# T5400_Barometer_Breakout-v01.net
KiCad netlist of a schematic drawn in EAGLE
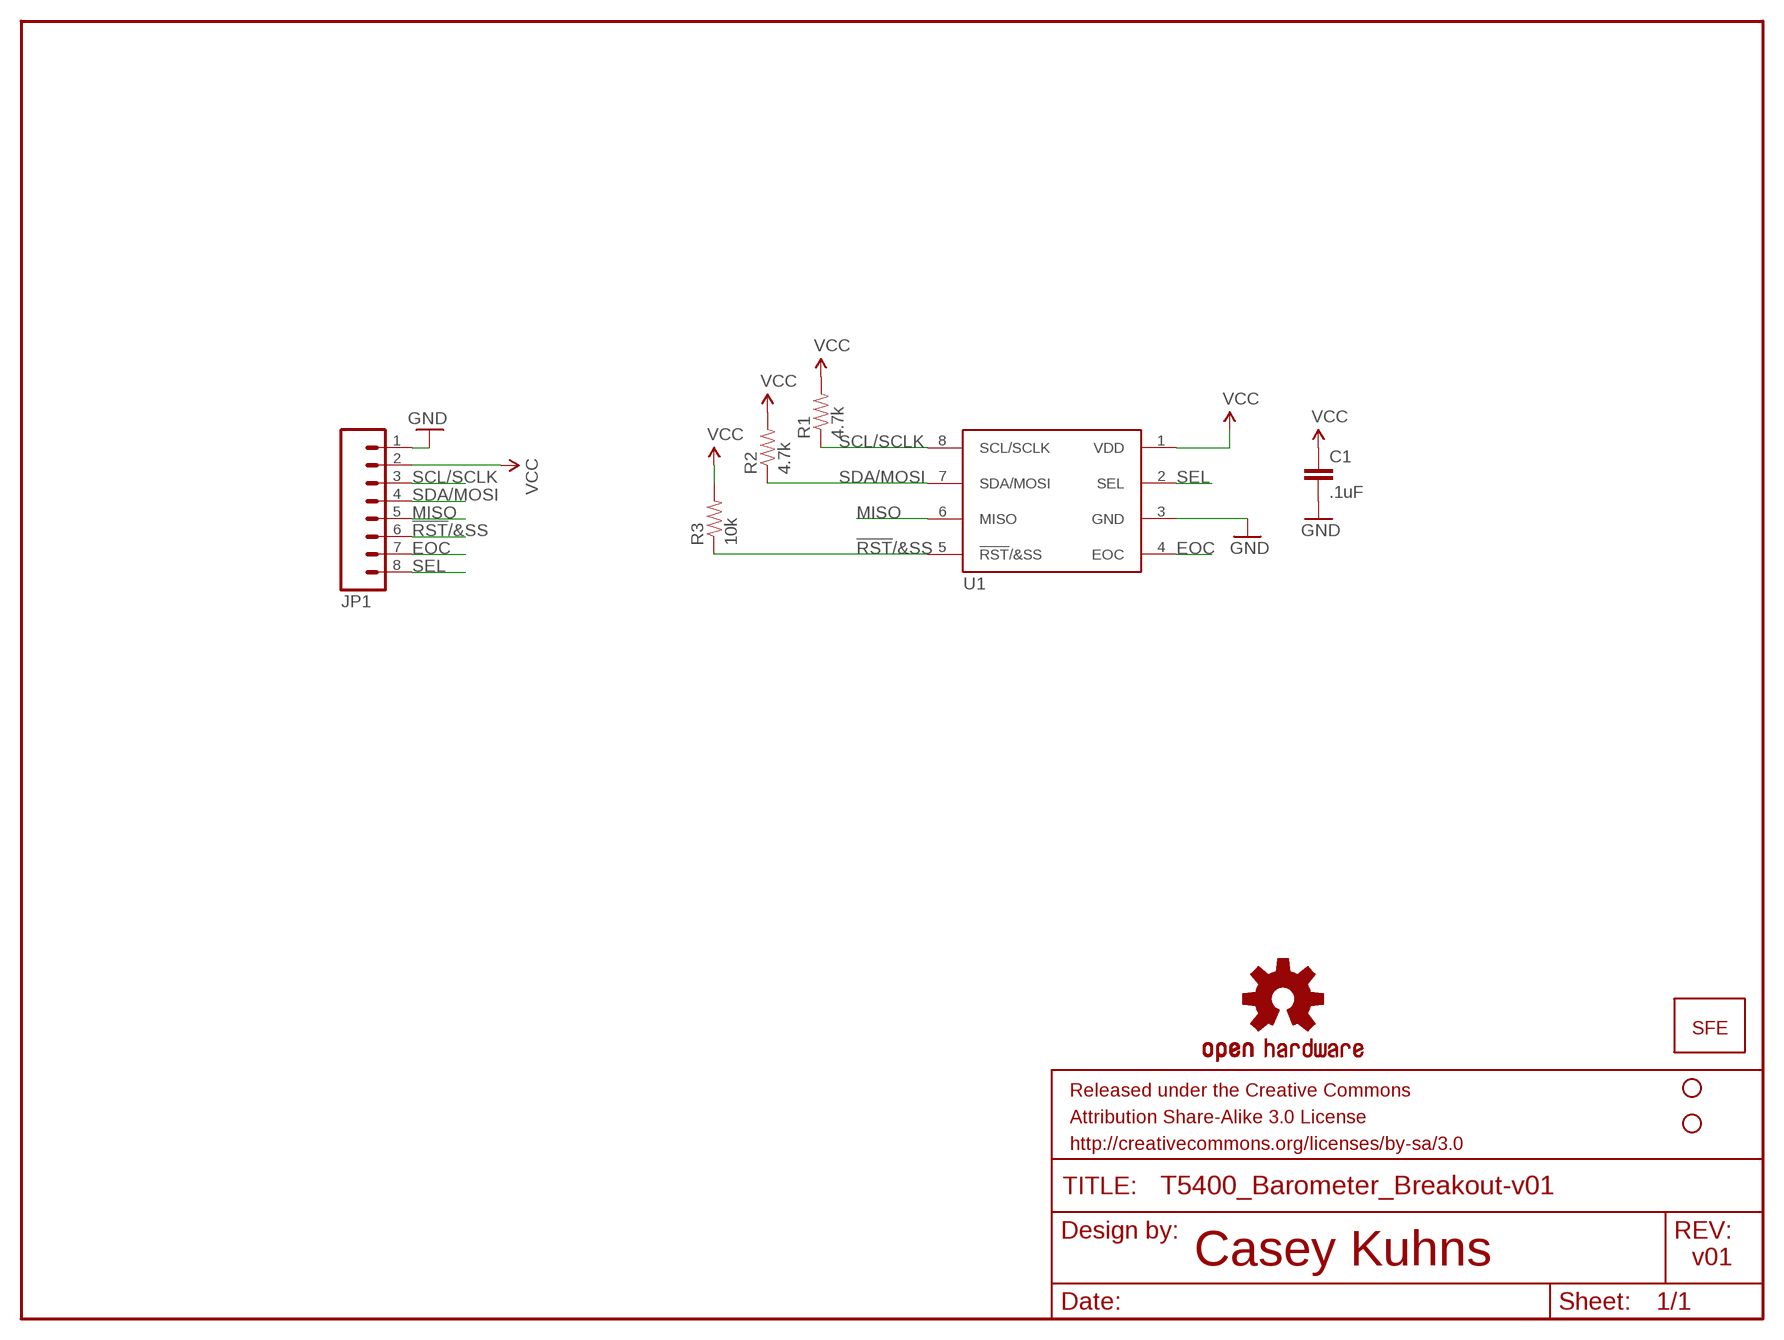
[diagram p0: schematic, sheet 1]

(export (version "E")
  (design (tool "Eeschema 10.0.6"))
  (components
    (comp (ref "C1")
      (value ".1uF")
      (footprint "eagle-import:0603-CAP")
      (libsource (lib "eagle-import") (part "0.1UF-25V-5%(0603)"))
    )
    (comp (ref "FRAME1")
      (value "FRAME-LETTER")
      (footprint "eagle-import:CREATIVE_COMMONS")
      (libsource (lib "eagle-import") (part "FRAME-LETTER"))
    )
    (comp (ref "JP1")
      (value "M081X08")
      (footprint "eagle-import:1X08")
      (libsource (lib "eagle-import") (part "M081X08"))
    )
    (comp (ref "LOGO1")
      (value "LOGO-SFENEW")
      (footprint "eagle-import:SFE-NEW-WEBLOGO")
      (libsource (lib "eagle-import") (part "LOGO-SFENEW"))
    )
    (comp (ref "LOGO2")
      (value "OSHW-LOGOS")
      (footprint "eagle-import:OSHW-LOGO-S")
      (libsource (lib "eagle-import") (part "OSHW-LOGOS"))
    )
    (comp (ref "R1")
      (value "4.7k")
      (footprint "eagle-import:0603-RES")
      (libsource (lib "eagle-import") (part "RESISTOR0603-RES"))
    )
    (comp (ref "R2")
      (value "4.7k")
      (footprint "eagle-import:0603-RES")
      (libsource (lib "eagle-import") (part "RESISTOR0603-RES"))
    )
    (comp (ref "R3")
      (value "10k")
      (footprint "eagle-import:0603-RES")
      (libsource (lib "eagle-import") (part "RESISTOR0603-RES"))
    )
    (comp (ref "STANDOFF1")
      (value "STAND-OFF")
      (footprint "eagle-import:STAND-OFF")
      (libsource (lib "eagle-import") (part "STAND-OFF"))
    )
    (comp (ref "STANDOFF2")
      (value "STAND-OFF")
      (footprint "eagle-import:STAND-OFF")
      (libsource (lib "eagle-import") (part "STAND-OFF"))
    )
    (comp (ref "U1")
      (value "T5400")
      (footprint "eagle-import:T5400")
      (libsource (lib "eagle-import") (part "T5400"))
    )
  )
  (nets
    (net (code "1") (name "/EOC") (class "Default")
      (node (ref "JP1") (pin "7") (pinfunction "7_7") (pintype "passive"))
      (node (ref "U1") (pin "4") (pinfunction "EOC_4") (pintype "bidirectional"))
    )
    (net (code "2") (name "/MISO") (class "Default")
      (node (ref "JP1") (pin "5") (pinfunction "5_5") (pintype "passive"))
      (node (ref "U1") (pin "6") (pinfunction "MISO_6") (pintype "bidirectional"))
    )
    (net (code "3") (name "/SCL{slash}SCLK") (class "Default")
      (node (ref "JP1") (pin "3") (pinfunction "3_3") (pintype "passive"))
      (node (ref "R1") (pin "1") (pinfunction "1_1") (pintype "passive"))
      (node (ref "U1") (pin "8") (pinfunction "SCL/SCLK_8") (pintype "bidirectional"))
    )
    (net (code "4") (name "/SDA{slash}MOSI") (class "Default")
      (node (ref "JP1") (pin "4") (pinfunction "4_4") (pintype "passive"))
      (node (ref "R2") (pin "1") (pinfunction "1_1") (pintype "passive"))
      (node (ref "U1") (pin "7") (pinfunction "SDA/MOSI_7") (pintype "bidirectional"))
    )
    (net (code "5") (name "/SEL") (class "Default")
      (node (ref "JP1") (pin "8") (pinfunction "8_8") (pintype "passive"))
      (node (ref "U1") (pin "2") (pinfunction "SEL_2") (pintype "bidirectional"))
    )
    (net (code "6") (name "/~{RST}{slash}&SS") (class "Default")
      (node (ref "JP1") (pin "6") (pinfunction "6_6") (pintype "passive"))
      (node (ref "R3") (pin "1") (pinfunction "1_1") (pintype "passive"))
      (node (ref "U1") (pin "5") (pinfunction "~{RST}/&SS_5") (pintype "bidirectional"))
    )
    (net (code "7") (name "GND") (class "Default")
      (node (ref "C1") (pin "2") (pinfunction "2_2") (pintype "passive"))
      (node (ref "JP1") (pin "1") (pinfunction "1_1") (pintype "passive"))
      (node (ref "U1") (pin "3") (pinfunction "GND_3") (pintype "bidirectional"))
    )
    (net (code "8") (name "VCC") (class "Default")
      (node (ref "C1") (pin "1") (pinfunction "1_1") (pintype "passive"))
      (node (ref "JP1") (pin "2") (pinfunction "2_2") (pintype "passive"))
      (node (ref "R1") (pin "2") (pinfunction "2_2") (pintype "passive"))
      (node (ref "R2") (pin "2") (pinfunction "2_2") (pintype "passive"))
      (node (ref "R3") (pin "2") (pinfunction "2_2") (pintype "passive"))
      (node (ref "U1") (pin "1") (pinfunction "VDD_1") (pintype "bidirectional"))
    )
  )
)
